# PV_BMS_IO.net
KiCad netlist of a schematic drawn in Altium Designer
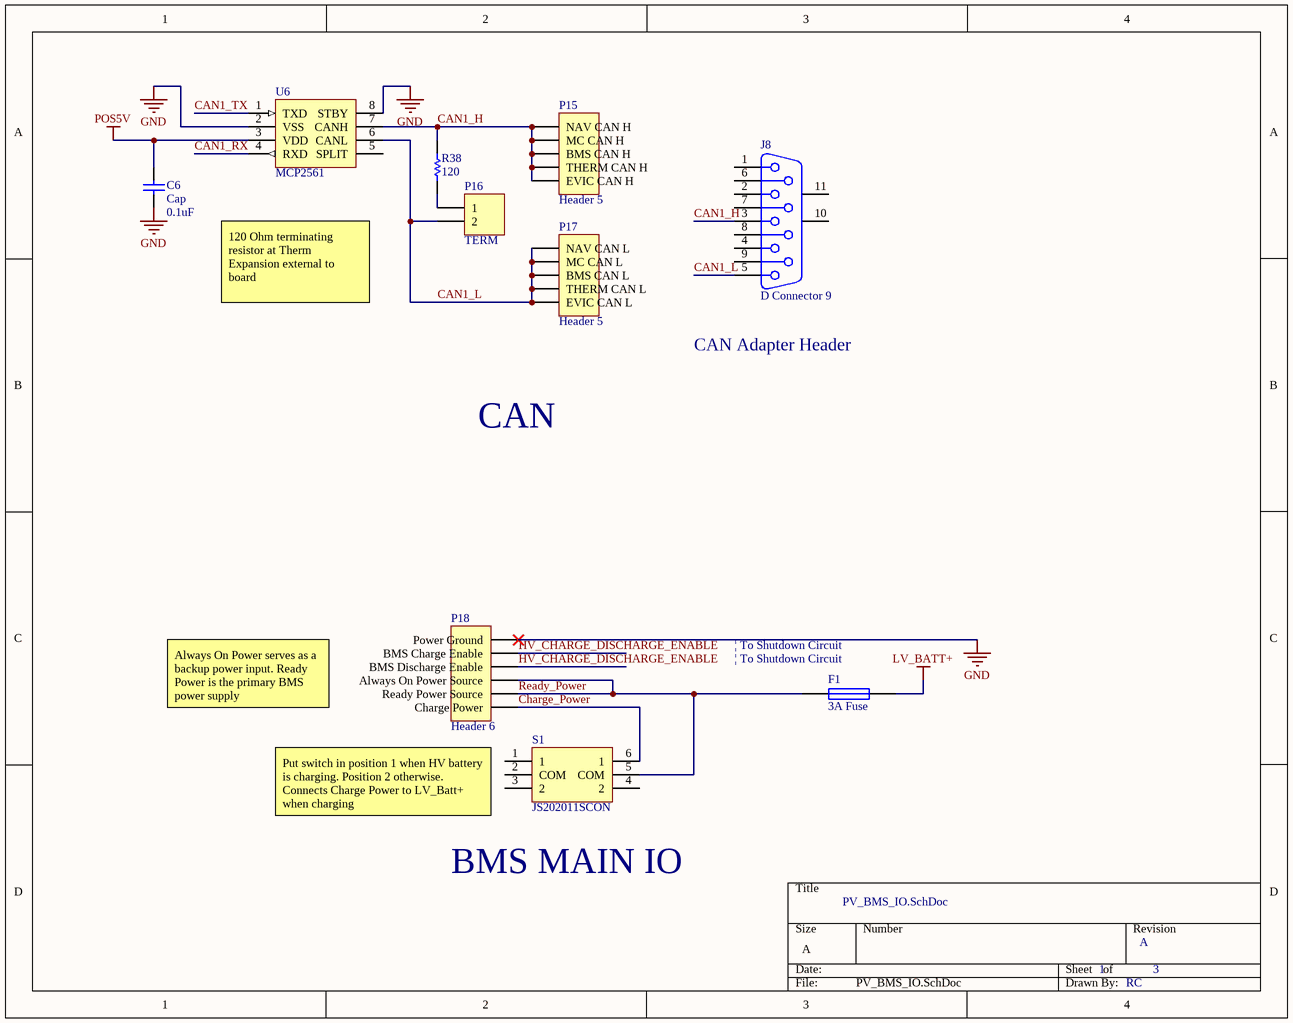
[diagram p0: PV_BMS_IO.SchDoc]

(export (version "E")
  (design (tool "Eeschema 10.0.6"))
  (components
    (comp (ref "C6")
      (value "Cap")
      (footprint "1206")
      (description "Capacitor")
      (fields (field (name "ALTIUM_VALUE") "0.1uF") (field (name "PUBLISHER") "Altium Limited"))
      (libsource (lib "Miscellaneous Devices") (part "Cap"))
    )
    (comp (ref "F1")
      (value "3A Fuse")
      (footprint "1A FUSE HOLDER")
      (description "Fuse")
      (fields (field (name "PUBLISHER") "Altium Limited"))
      (libsource (lib "Miscellaneous Devices") (part "Fuse 1"))
    )
    (comp (ref "J8")
      (value "D Connector 9")
      (footprint "DSUB1.385-2H9")
      (description "Receptacle Assembly, 9 Position, Right Angle")
      (fields (field (name "PUBLISHER") "Altium Limited"))
      (libsource (lib "Miscellaneous Connectors") (part "D Connector 9"))
    )
    (comp (ref "P15")
      (value "Header 5")
      (footprint "5POS TERM BLOCK")
      (description "Header, 5-Pin")
      (fields (field (name "PUBLISHER") "Altium Limited"))
      (libsource (lib "Miscellaneous Connectors") (part "Header 5"))
    )
    (comp (ref "P16")
      (value "TERM")
      (footprint "HDR1X2")
      (description "Header, 2-Pin")
      (fields (field (name "PUBLISHER") "Altium Limited"))
      (libsource (lib "Miscellaneous Connectors") (part "Header 2"))
    )
    (comp (ref "P17")
      (value "Header 5")
      (footprint "5POS TERM BLOCK")
      (description "Header, 5-Pin")
      (fields (field (name "PUBLISHER") "Altium Limited"))
      (libsource (lib "Miscellaneous Connectors") (part "Header 5"))
    )
    (comp (ref "P18")
      (value "Header 6")
      (footprint "6POS TERM BLOCK")
      (description "Header, 6-Pin")
      (fields (field (name "PUBLISHER") "Altium Limited"))
      (libsource (lib "Miscellaneous Connectors") (part "Header 6"))
    )
    (comp (ref "R38")
      (value "120")
      (footprint "1206")
      (description "Resistor")
      (fields (field (name "Comment") "Res1") (field (name "PUBLISHER") "Altium Limited"))
      (libsource (lib "Miscellaneous Devices") (part "Res1"))
    )
    (comp (ref "S1")
      (value "JS202011SCON")
      (footprint "JS202011SCON")
      (description "DPST Switch")
      (libsource (lib "ic") (part "JS202011SCON"))
    )
    (comp (ref "U6")
      (value "MCP2561")
      (footprint "8-SOIC")
      (description "CAN Transciever")
      (libsource (lib "ic") (part "MCP2561"))
    )
  )
  (nets
    (net (code "1") (name "/CAN1_H") (class "Default")
      (node (ref "J8") (pin "3") (pinfunction "3_3") (pintype "passive"))
      (node (ref "P15") (pin "1") (pinfunction "NAV_CAN_H_1") (pintype "passive"))
      (node (ref "P15") (pin "2") (pinfunction "MC_CAN_H_2") (pintype "passive"))
      (node (ref "P15") (pin "3") (pinfunction "BMS_CAN_H_3") (pintype "passive"))
      (node (ref "P15") (pin "4") (pinfunction "THERM_CAN_H_4") (pintype "passive"))
      (node (ref "P15") (pin "5") (pinfunction "EVIC_CAN_H_5") (pintype "passive"))
      (node (ref "R38") (pin "2") (pinfunction "2_2") (pintype "passive"))
      (node (ref "U6") (pin "7") (pinfunction "CANH_7") (pintype "passive"))
    )
    (net (code "2") (name "/CAN1_L") (class "Default")
      (node (ref "J8") (pin "5") (pinfunction "5_5") (pintype "passive"))
      (node (ref "P16") (pin "2") (pinfunction "2_2") (pintype "passive"))
      (node (ref "P17") (pin "1") (pinfunction "NAV_CAN_H_1") (pintype "passive"))
      (node (ref "P17") (pin "2") (pinfunction "MC_CAN_H_2") (pintype "passive"))
      (node (ref "P17") (pin "3") (pinfunction "BMS_CAN_H_3") (pintype "passive"))
      (node (ref "P17") (pin "4") (pinfunction "THERM_CAN_H_4") (pintype "passive"))
      (node (ref "P17") (pin "5") (pinfunction "EVIC_CAN_H_5") (pintype "passive"))
      (node (ref "U6") (pin "6") (pinfunction "CANL_6") (pintype "passive"))
    )
    (net (code "3") (name "/CAN1_RX") (class "Default")
      (node (ref "U6") (pin "4") (pinfunction "RXD_4") (pintype "output"))
    )
    (net (code "4") (name "/CAN1_TX") (class "Default")
      (node (ref "U6") (pin "1") (pinfunction "TXD_1") (pintype "input"))
    )
    (net (code "5") (name "/Charge_Power") (class "Default")
      (node (ref "P18") (pin "1") (pinfunction "Charge_Power_1") (pintype "passive"))
      (node (ref "S1") (pin "6") (pinfunction "1_6") (pintype "passive"))
    )
    (net (code "6") (name "/HV_CHARGE_DISCHARGE_ENABLE") (class "Default")
      (node (ref "P18") (pin "4") (pinfunction "BMS_Discharge_Enable_4") (pintype "passive"))
      (node (ref "P18") (pin "5") (pinfunction "BMS_Charge_Enable_5") (pintype "passive"))
    )
    (net (code "7") (name "/Ready_Power") (class "Default")
      (node (ref "F1") (pin "1") (pinfunction "1_1") (pintype "passive"))
      (node (ref "P18") (pin "2") (pinfunction "Ready_Power_Source_2") (pintype "passive"))
      (node (ref "P18") (pin "3") (pinfunction "Always_On_Power_Source_3") (pintype "passive"))
      (node (ref "S1") (pin "5") (pinfunction "COM_5") (pintype "passive"))
    )
    (net (code "8") (name "GND") (class "Default")
      (node (ref "C6") (pin "1") (pinfunction "1_1") (pintype "passive"))
      (node (ref "P18") (pin "6") (pinfunction "Power_Ground_6") (pintype "passive"))
      (node (ref "U6") (pin "2") (pinfunction "VSS_2") (pintype "passive"))
      (node (ref "U6") (pin "8") (pinfunction "STBY_8") (pintype "passive"))
    )
    (net (code "9") (name "LV_BATT+") (class "Default")
      (node (ref "F1") (pin "2") (pinfunction "2_2") (pintype "passive"))
    )
    (net (code "10") (name "Net-(P16-Pad1)") (class "Default")
      (node (ref "P16") (pin "1") (pinfunction "1_1") (pintype "passive"))
      (node (ref "R38") (pin "1") (pinfunction "1_1") (pintype "passive"))
    )
    (net (code "11") (name "POS5V") (class "Default")
      (node (ref "C6") (pin "2") (pinfunction "2_2") (pintype "passive"))
      (node (ref "U6") (pin "3") (pinfunction "VDD_3") (pintype "passive"))
    )
    (net (code "12") (name "unconnected-(J8-MH1-Pad10)") (class "Default")
      (node (ref "J8") (pin "10") (pinfunction "MH1_10") (pintype "passive"))
    )
    (net (code "13") (name "unconnected-(J8-MH2-Pad11)") (class "Default")
      (node (ref "J8") (pin "11") (pinfunction "MH2_11") (pintype "passive"))
    )
    (net (code "14") (name "unconnected-(J8-Pad1)") (class "Default")
      (node (ref "J8") (pin "1") (pinfunction "1_1") (pintype "passive"))
    )
    (net (code "15") (name "unconnected-(J8-Pad2)") (class "Default")
      (node (ref "J8") (pin "2") (pinfunction "2_2") (pintype "passive"))
    )
    (net (code "16") (name "unconnected-(J8-Pad4)") (class "Default")
      (node (ref "J8") (pin "4") (pinfunction "4_4") (pintype "passive"))
    )
    (net (code "17") (name "unconnected-(J8-Pad6)") (class "Default")
      (node (ref "J8") (pin "6") (pinfunction "6_6") (pintype "passive"))
    )
    (net (code "18") (name "unconnected-(J8-Pad7)") (class "Default")
      (node (ref "J8") (pin "7") (pinfunction "7_7") (pintype "passive"))
    )
    (net (code "19") (name "unconnected-(J8-Pad8)") (class "Default")
      (node (ref "J8") (pin "8") (pinfunction "8_8") (pintype "passive"))
    )
    (net (code "20") (name "unconnected-(J8-Pad9)") (class "Default")
      (node (ref "J8") (pin "9") (pinfunction "9_9") (pintype "passive"))
    )
    (net (code "21") (name "unconnected-(S1-2-Pad3)") (class "Default")
      (node (ref "S1") (pin "3") (pinfunction "2_3") (pintype "passive"))
    )
    (net (code "22") (name "unconnected-(S1-2-Pad4)") (class "Default")
      (node (ref "S1") (pin "4") (pinfunction "2_4") (pintype "passive"))
    )
    (net (code "23") (name "unconnected-(S1-COM-Pad2)") (class "Default")
      (node (ref "S1") (pin "2") (pinfunction "COM_2") (pintype "passive"))
    )
    (net (code "24") (name "unconnected-(S1-Pad1)") (class "Default")
      (node (ref "S1") (pin "1") (pinfunction "1_1") (pintype "passive"))
    )
    (net (code "25") (name "unconnected-(U6-SPLIT-Pad5)") (class "Default")
      (node (ref "U6") (pin "5") (pinfunction "SPLIT_5") (pintype "passive"))
    )
  )
)
